# Motor-Driver.net
KiCad netlist of a schematic drawn in EAGLE
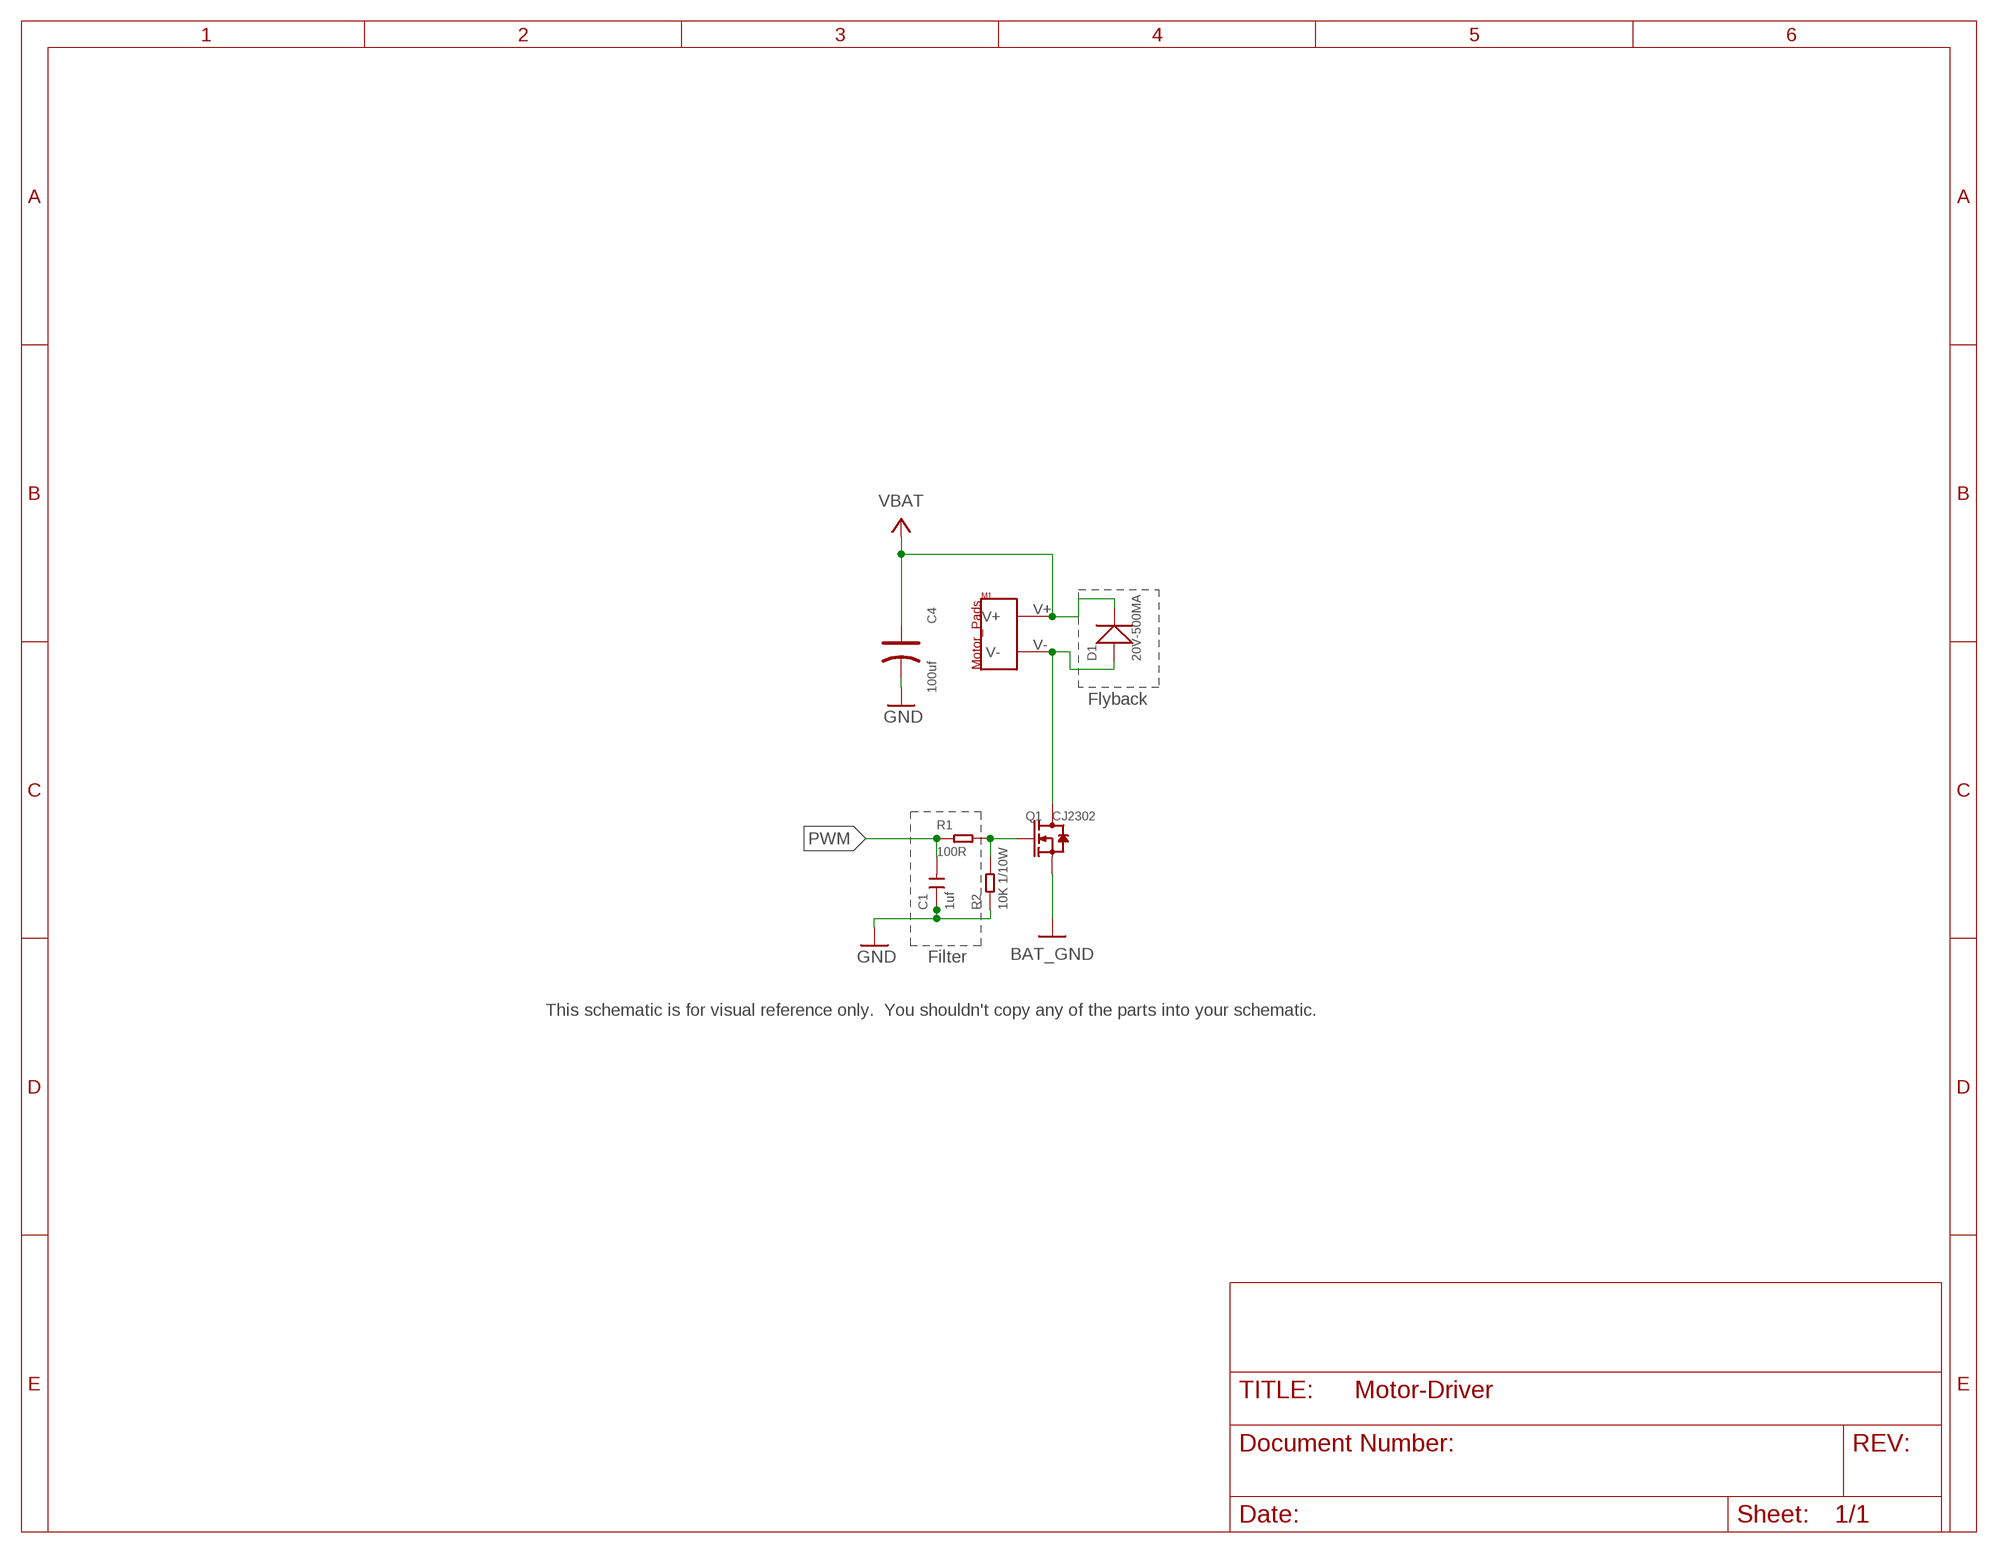
[diagram p0: schematic, sheet 1]

(export (version "E")
  (design (tool "Eeschema 10.0.6"))
  (components
    (comp (ref "C1")
      (value "1uf")
      (footprint "eagle-import:C0402")
      (fields (field (name "MPN") "CC0402KRX5R6BB105"))
      (libsource (lib "eagle-import") (part "CERAMIC-1UF-10V-10%-X5R(0402)"))
    )
    (comp (ref "C4")
      (value "100uf")
      (footprint "eagle-import:AVX-B")
      (fields (field (name "MPN") "TAJB107M010#NJ"))
      (libsource (lib "eagle-import") (part "TANTALUM-SMD-100UF-10V(AVX-B)"))
    )
    (comp (ref "D1")
      (value "20V-500MA")
      (footprint "eagle-import:SOD-123")
      (fields (field (name "MPN") "SS0520-7-F"))
      (libsource (lib "eagle-import") (part "SMD-DIODE-SCHOTTKY-20V-500MA(SOD-123)"))
    )
    (comp (ref "M1")
      (value "MOTOR_PADS")
      (footprint "eagle-import:MOTOR_PADS")
      (libsource (lib "eagle-import") (part "MOTOR_PADS"))
    )
    (comp (ref "Q1")
      (value "CJ2302")
      (footprint "eagle-import:SOT-23")
      (libsource (lib "eagle-import") (part "SMD-MOSFET-N-CH-20V-2.1A-CJ2302(SOT-23)"))
    )
    (comp (ref "R1")
      (value "100R")
      (footprint "eagle-import:R0603")
      (fields (field (name "MPN") "RC0603JR-07100RL"))
      (libsource (lib "eagle-import") (part "SMD-RES-100R-5%-1/10W(0603)"))
    )
    (comp (ref "R2")
      (value "10K 1/10W")
      (footprint "eagle-import:R0603")
      (fields (field (name "MPN") "RC0603JR-0710KL"))
      (libsource (lib "eagle-import") (part "SMD-RES-10K-5%-1/10W(0603)"))
    )
  )
  (nets
    (net (code "1") (name "BAT_GND") (class "Default")
      (node (ref "Q1") (pin "2") (pinfunction "S_2") (pintype "passive"))
    )
    (net (code "2") (name "GND") (class "Default")
      (node (ref "C1") (pin "1") (pinfunction "1_1") (pintype "passive"))
      (node (ref "C4") (pin "-") (pinfunction "-_-") (pintype "passive"))
      (node (ref "R2") (pin "1") (pinfunction "1_1") (pintype "passive"))
    )
    (net (code "3") (name "Net-(Q1-D)") (class "Default")
      (node (ref "D1") (pin "+") (pinfunction "+_+") (pintype "passive"))
      (node (ref "M1") (pin "V-") (pinfunction "V-_V-") (pintype "bidirectional"))
      (node (ref "Q1") (pin "3") (pinfunction "D_3") (pintype "passive"))
    )
    (net (code "4") (name "Net-(Q1-G)") (class "Default")
      (node (ref "Q1") (pin "1") (pinfunction "G_1") (pintype "passive"))
      (node (ref "R1") (pin "2") (pinfunction "2_2") (pintype "passive"))
      (node (ref "R2") (pin "2") (pinfunction "2_2") (pintype "passive"))
    )
    (net (code "5") (name "PWM") (class "Default")
      (node (ref "C1") (pin "2") (pinfunction "2_2") (pintype "passive"))
      (node (ref "R1") (pin "1") (pinfunction "1_1") (pintype "passive"))
    )
    (net (code "6") (name "VBAT") (class "Default")
      (node (ref "C4") (pin "+") (pinfunction "+_+") (pintype "passive"))
      (node (ref "D1") (pin "-") (pinfunction "-_-") (pintype "passive"))
      (node (ref "M1") (pin "V+") (pinfunction "V+_V+") (pintype "bidirectional"))
    )
  )
)
